# SCH_ESP_weather_Cube_2022-04-20.net
KiCad netlist of a schematic drawn in EasyEDA
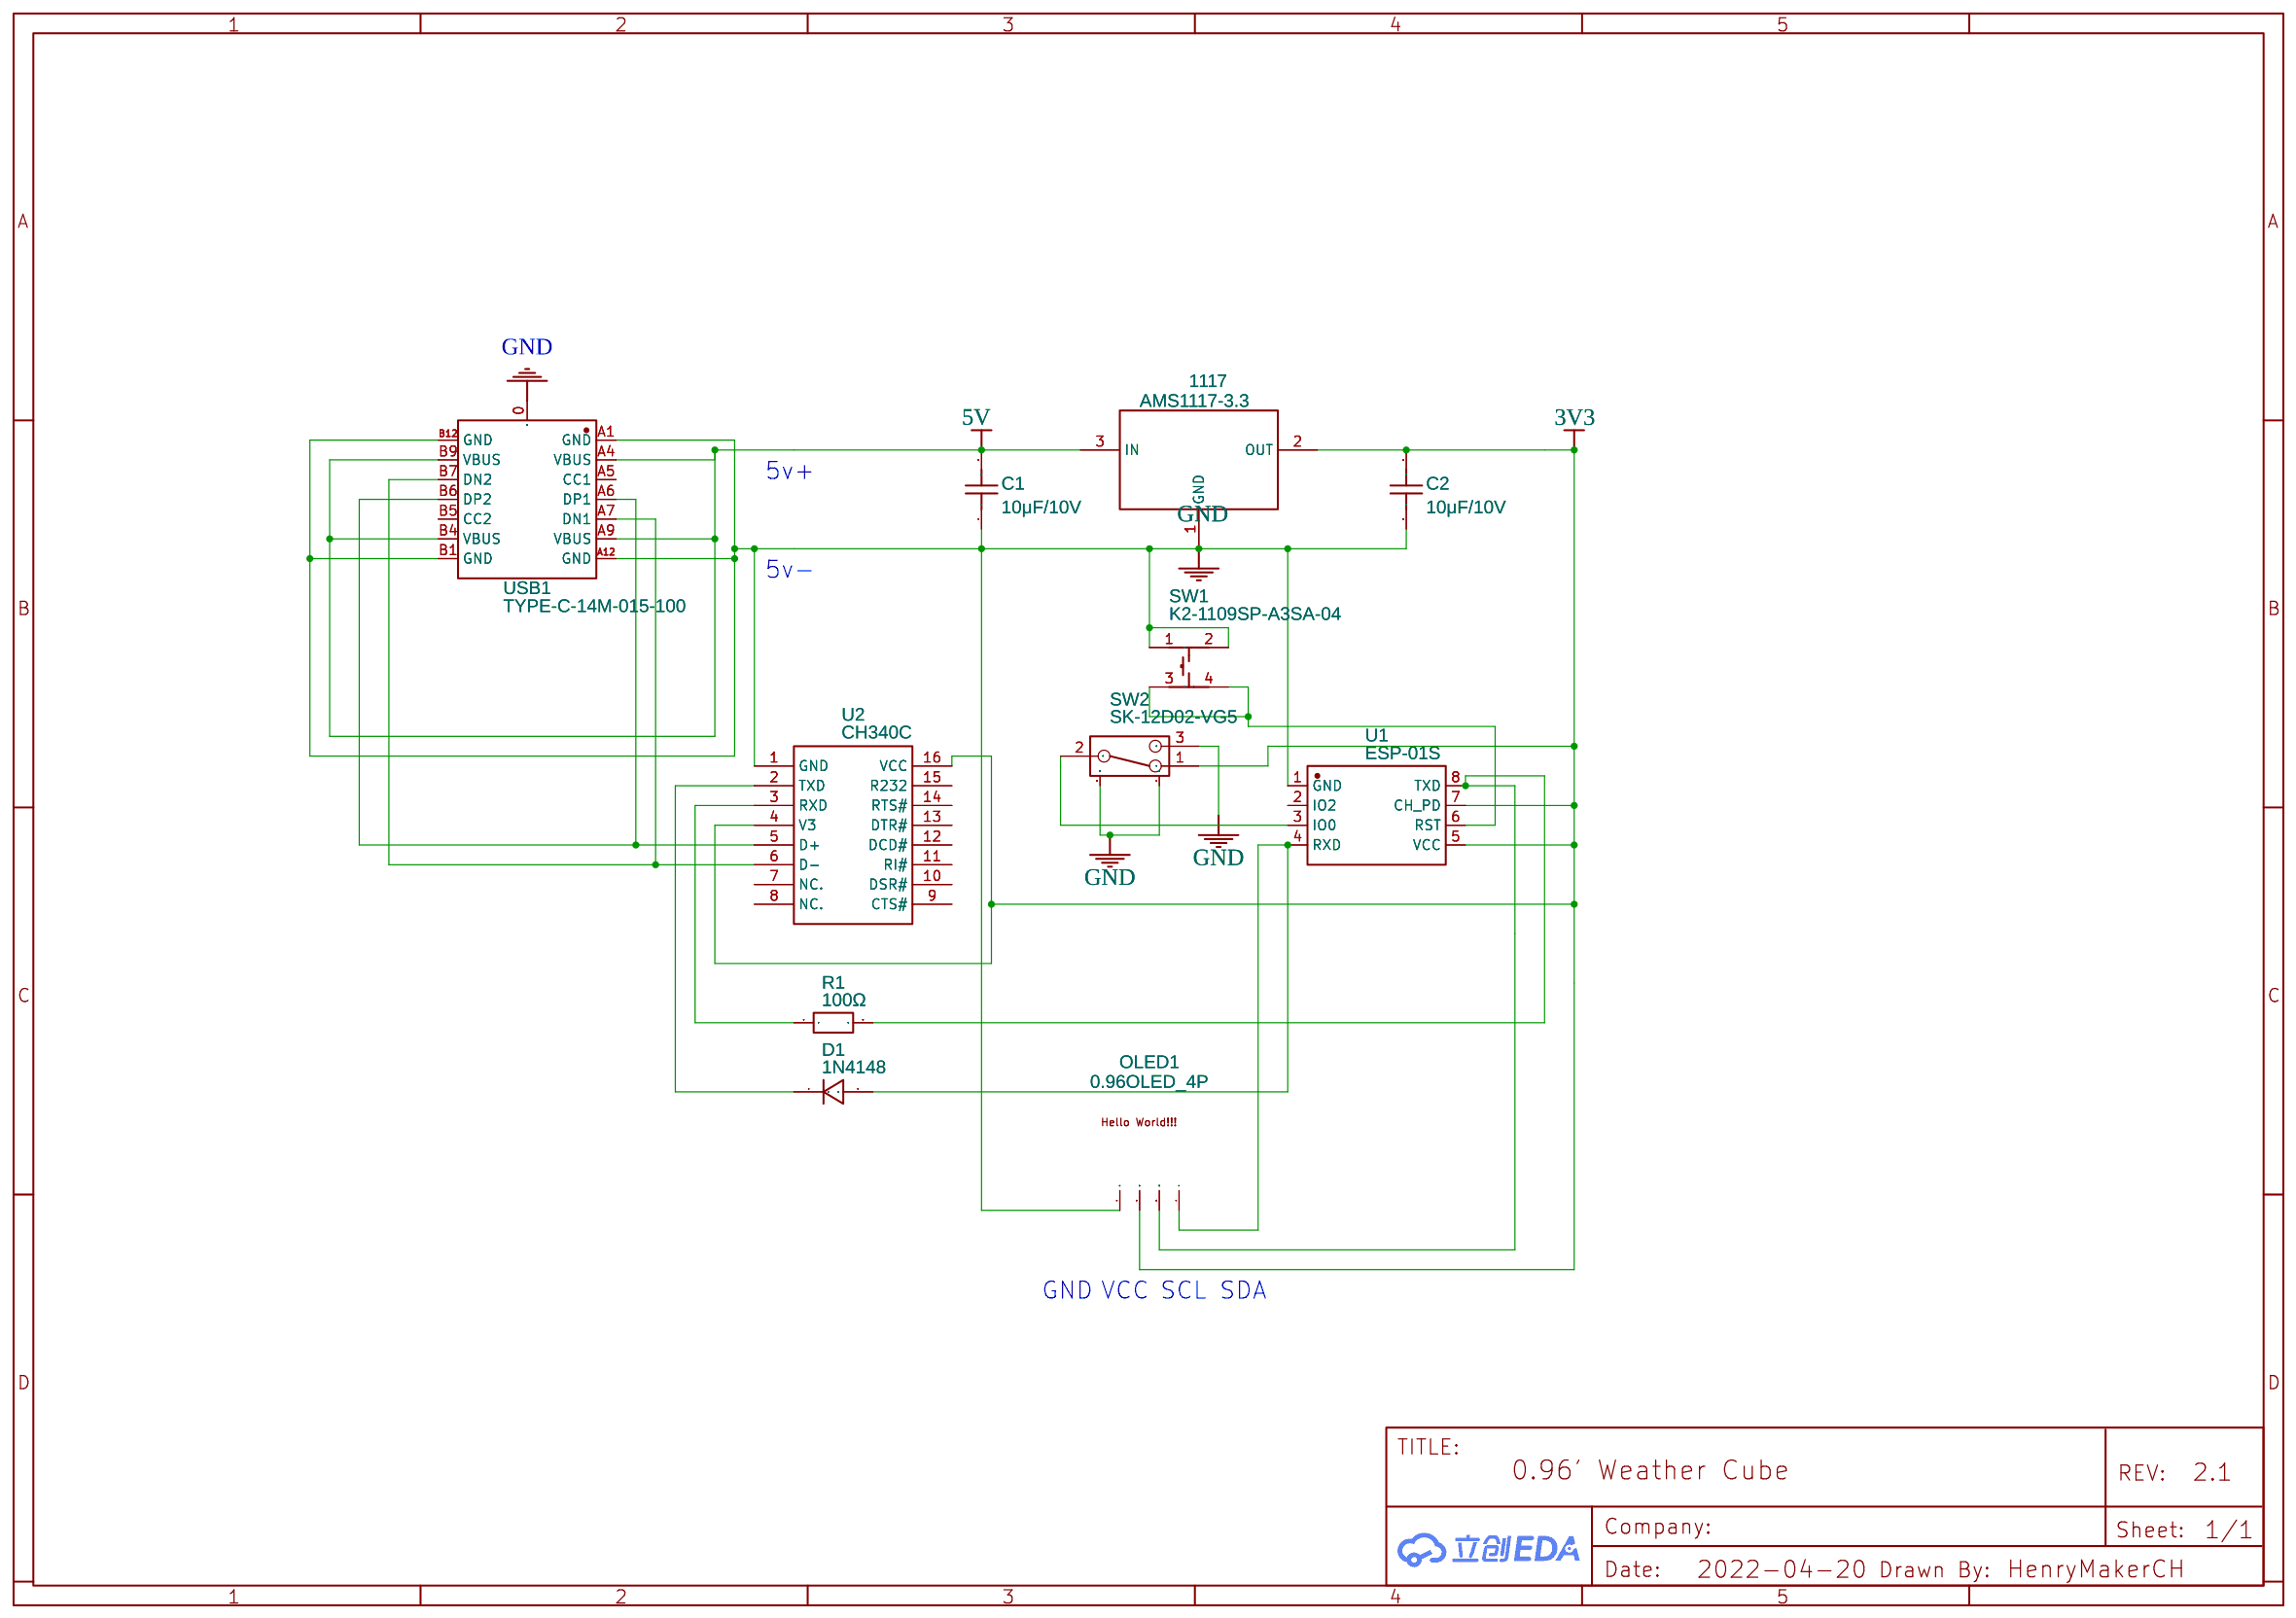
[diagram p0: schematic sheet]

(export (version "E")
  (design (tool "Eeschema 10.0.6"))
  (components
    (comp (ref "1117") (value "AMS1117-3.3") (libsource (lib "") (part "Unknown_560_-605")))
    (comp (ref "C1") (value "10μF/10V") (libsource (lib "") (part "Capacitor")))
    (comp (ref "C2") (value "10μF/10V") (libsource (lib "") (part "Capacitor")))
    (comp (ref "D1")
      (value "1N4148")
      (fields (field (name "BOM_Supplier Part") "C13769"))
      (libsource (lib "") (part "1N4148_C13769"))
    )
    (comp (ref "OLED1") (value "0.96OLED_4P") (libsource (lib "") (part "0.96OLED_4P")))
    (comp (ref "R1") (value "100Ω") (libsource (lib "") (part "R_0603_EU")))
    (comp (ref "SW1")
      (value "K2-1109SP-A3SA-04")
      (fields (field (name "BOM_Supplier Part") "C516447"))
      (libsource (lib "") (part "K2-1109SP-A3SA-04"))
    )
    (comp (ref "SW2")
      (value "SK-12D02-VG5")
      (fields (field (name "BOM_Supplier Part") "C136722"))
      (libsource (lib "") (part "SK-12D02-VG5"))
    )
    (comp (ref "U1")
      (value "ESP-01S")
      (fields (field (name "BOM_Supplier Part") "C111009"))
      (libsource (lib "") (part "ESP-01S"))
    )
    (comp (ref "U2")
      (value "CH340C")
      (fields (field (name "BOM_Supplier Part") "C84681"))
      (libsource (lib "") (part "CH340C"))
    )
    (comp (ref "USB1")
      (value "TYPE-C-14M-015-100")
      (fields (field (name "BOM_Supplier Part") "C2798183"))
      (libsource (lib "") (part "TYPE-C-14M-015-100"))
    )
  )
  (nets
    (net (code "1") (name "3V3") (class "Default")
      (node (ref "1117") (pin "2") (pinfunction "OUT_2") (pintype "unspecified"))
      (node (ref "C2") (pin "2") (pinfunction "2_2") (pintype "unspecified"))
      (node (ref "OLED1") (pin "2") (pinfunction "2_2") (pintype "unspecified"))
      (node (ref "SW2") (pin "1") (pinfunction "1_1") (pintype "unspecified"))
      (node (ref "U1") (pin "5") (pinfunction "VCC_5") (pintype "unspecified"))
      (node (ref "U1") (pin "7") (pinfunction "CH_PD_7") (pintype "unspecified"))
      (node (ref "U2") (pin "16") (pinfunction "VCC_16") (pintype "unspecified"))
      (node (ref "U2") (pin "4") (pinfunction "V3_4") (pintype "unspecified"))
    )
    (net (code "2") (name "5V") (class "Default")
      (node (ref "1117") (pin "3") (pinfunction "IN_3") (pintype "unspecified"))
      (node (ref "C1") (pin "2") (pinfunction "2_2") (pintype "unspecified"))
      (node (ref "USB1") (pin "A4") (pinfunction "VBUS_A4") (pintype "unspecified"))
      (node (ref "USB1") (pin "A9") (pinfunction "VBUS_A9") (pintype "unspecified"))
      (node (ref "USB1") (pin "B4") (pinfunction "VBUS_B4") (pintype "unspecified"))
      (node (ref "USB1") (pin "B9") (pinfunction "VBUS_B9") (pintype "unspecified"))
    )
    (net (code "3") (name "GND") (class "Default")
      (node (ref "1117") (pin "1") (pinfunction "GND_1") (pintype "unspecified"))
      (node (ref "C1") (pin "1") (pinfunction "1_1") (pintype "unspecified"))
      (node (ref "C2") (pin "1") (pinfunction "1_1") (pintype "unspecified"))
      (node (ref "OLED1") (pin "1") (pinfunction "1_1") (pintype "unspecified"))
      (node (ref "SW1") (pin "1") (pinfunction "1_1") (pintype "unspecified"))
      (node (ref "SW1") (pin "2") (pinfunction "2_2") (pintype "unspecified"))
      (node (ref "SW2") (pin "3") (pinfunction "3_3") (pintype "unspecified"))
      (node (ref "SW2") (pin "4") (pinfunction "4_4") (pintype "unspecified"))
      (node (ref "SW2") (pin "5") (pinfunction "5_5") (pintype "unspecified"))
      (node (ref "U1") (pin "1") (pinfunction "GND_1") (pintype "unspecified"))
      (node (ref "U2") (pin "1") (pinfunction "GND_1") (pintype "unspecified"))
      (node (ref "USB1") (pin "0") (pinfunction "0_0") (pintype "unspecified"))
      (node (ref "USB1") (pin "A1") (pinfunction "GND_A1") (pintype "unspecified"))
      (node (ref "USB1") (pin "A12") (pinfunction "GND_A12") (pintype "unspecified"))
      (node (ref "USB1") (pin "B1") (pinfunction "GND_B1") (pintype "unspecified"))
      (node (ref "USB1") (pin "B12") (pinfunction "GND_B12") (pintype "unspecified"))
    )
    (net (code "4") (name "Net-(U1-IO0)") (class "Default")
      (node (ref "SW2") (pin "2") (pinfunction "2_2") (pintype "unspecified"))
      (node (ref "U1") (pin "3") (pinfunction "IO0_3") (pintype "unspecified"))
    )
    (net (code "5") (name "Net-(U1-RST)") (class "Default")
      (node (ref "SW1") (pin "3") (pinfunction "3_3") (pintype "unspecified"))
      (node (ref "SW1") (pin "4") (pinfunction "4_4") (pintype "unspecified"))
      (node (ref "U1") (pin "6") (pinfunction "RST_6") (pintype "unspecified"))
    )
    (net (code "6") (name "Net-(U1-RXD)") (class "Default")
      (node (ref "D1") (pin "2") (pinfunction "2_2") (pintype "unspecified"))
      (node (ref "OLED1") (pin "4") (pinfunction "4_4") (pintype "unspecified"))
      (node (ref "U1") (pin "4") (pinfunction "RXD_4") (pintype "unspecified"))
    )
    (net (code "7") (name "Net-(U1-TXD)") (class "Default")
      (node (ref "OLED1") (pin "3") (pinfunction "3_3") (pintype "unspecified"))
      (node (ref "R1") (pin "2") (pinfunction "2_2") (pintype "unspecified"))
      (node (ref "U1") (pin "8") (pinfunction "TXD_8") (pintype "unspecified"))
    )
    (net (code "8") (name "Net-(U2-D+)") (class "Default")
      (node (ref "U2") (pin "5") (pinfunction "D+_5") (pintype "unspecified"))
      (node (ref "USB1") (pin "A6") (pinfunction "DP1_A6") (pintype "unspecified"))
      (node (ref "USB1") (pin "B6") (pinfunction "DP2_B6") (pintype "unspecified"))
    )
    (net (code "9") (name "Net-(U2-D-)") (class "Default")
      (node (ref "U2") (pin "6") (pinfunction "D-_6") (pintype "unspecified"))
      (node (ref "USB1") (pin "A7") (pinfunction "DN1_A7") (pintype "unspecified"))
      (node (ref "USB1") (pin "B7") (pinfunction "DN2_B7") (pintype "unspecified"))
    )
    (net (code "10") (name "Net-(U2-RXD)") (class "Default")
      (node (ref "R1") (pin "1") (pinfunction "1_1") (pintype "unspecified"))
      (node (ref "U2") (pin "3") (pinfunction "RXD_3") (pintype "unspecified"))
    )
    (net (code "11") (name "Net-(U2-TXD)") (class "Default")
      (node (ref "D1") (pin "1") (pinfunction "1_1") (pintype "unspecified"))
      (node (ref "U2") (pin "2") (pinfunction "TXD_2") (pintype "unspecified"))
    )
    (net (code "12") (name "unconnected-(U1-IO2-Pad2)") (class "Default")
      (node (ref "U1") (pin "2") (pinfunction "IO2_2") (pintype "unspecified"))
    )
    (net (code "13") (name "unconnected-(U2-CTS#-Pad9)") (class "Default")
      (node (ref "U2") (pin "9") (pinfunction "CTS#_9") (pintype "unspecified"))
    )
    (net (code "14") (name "unconnected-(U2-DCD#-Pad12)") (class "Default")
      (node (ref "U2") (pin "12") (pinfunction "DCD#_12") (pintype "unspecified"))
    )
    (net (code "15") (name "unconnected-(U2-DSR#-Pad10)") (class "Default")
      (node (ref "U2") (pin "10") (pinfunction "DSR#_10") (pintype "unspecified"))
    )
    (net (code "16") (name "unconnected-(U2-DTR#-Pad13)") (class "Default")
      (node (ref "U2") (pin "13") (pinfunction "DTR#_13") (pintype "unspecified"))
    )
    (net (code "17") (name "unconnected-(U2-NC.-Pad7)") (class "Default")
      (node (ref "U2") (pin "7") (pinfunction "NC._7") (pintype "unspecified"))
    )
    (net (code "18") (name "unconnected-(U2-NC.-Pad8)") (class "Default")
      (node (ref "U2") (pin "8") (pinfunction "NC._8") (pintype "unspecified"))
    )
    (net (code "19") (name "unconnected-(U2-R232-Pad15)") (class "Default")
      (node (ref "U2") (pin "15") (pinfunction "R232_15") (pintype "unspecified"))
    )
    (net (code "20") (name "unconnected-(U2-RI#-Pad11)") (class "Default")
      (node (ref "U2") (pin "11") (pinfunction "RI#_11") (pintype "unspecified"))
    )
    (net (code "21") (name "unconnected-(U2-RTS#-Pad14)") (class "Default")
      (node (ref "U2") (pin "14") (pinfunction "RTS#_14") (pintype "unspecified"))
    )
    (net (code "22") (name "unconnected-(USB1-CC1-PadA5)") (class "Default")
      (node (ref "USB1") (pin "A5") (pinfunction "CC1_A5") (pintype "unspecified"))
    )
    (net (code "23") (name "unconnected-(USB1-CC2-PadB5)") (class "Default")
      (node (ref "USB1") (pin "B5") (pinfunction "CC2_B5") (pintype "unspecified"))
    )
  )
)
